# Power_Distribution_Board.net
KiCad netlist of a schematic drawn in EAGLE
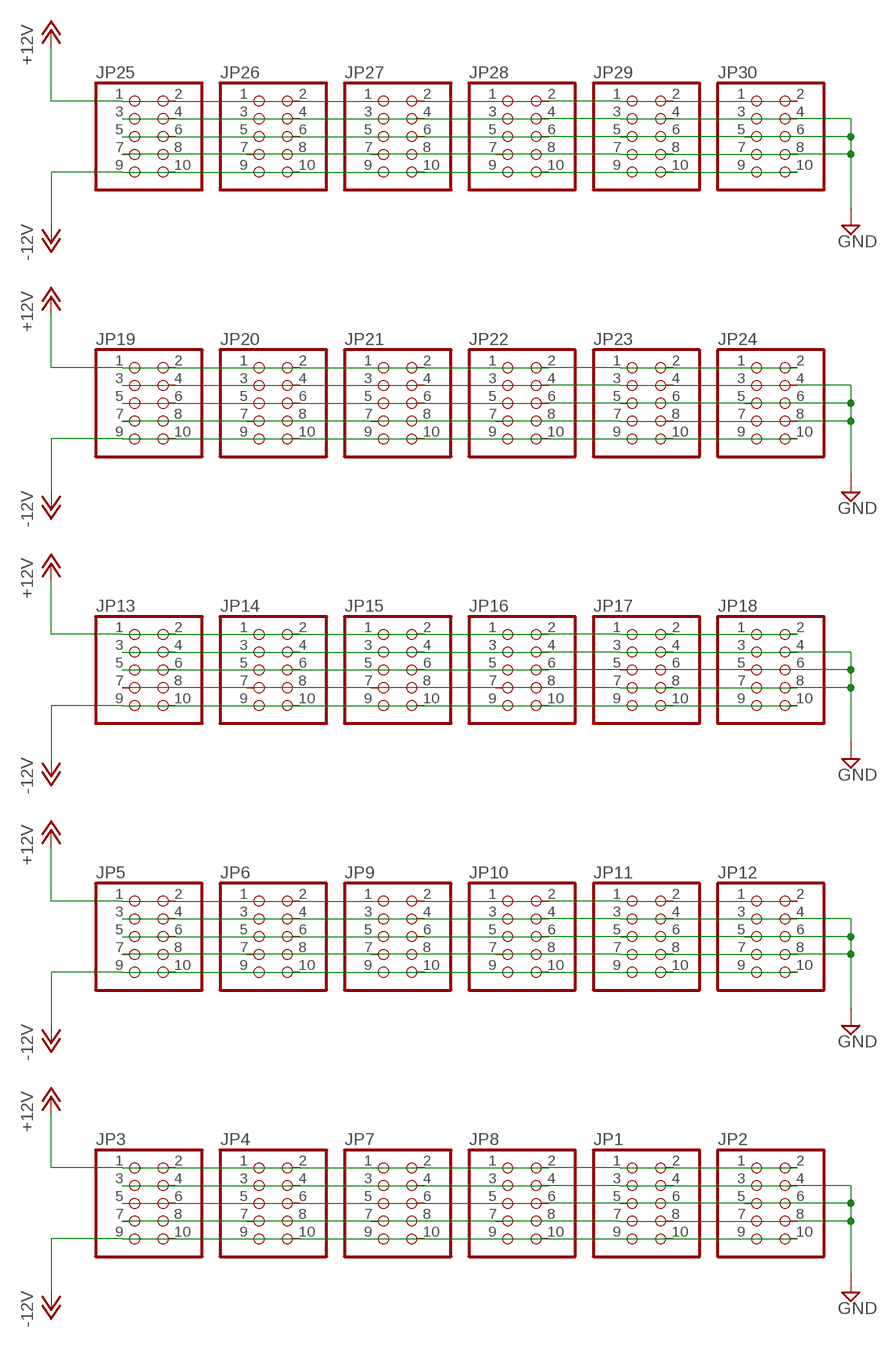
[diagram p0: schematic, sheet 1]

(export (version "E")
  (design (tool "Eeschema 10.0.6"))
  (components
    (comp (ref "JP1")
      (value "PINHD-2X5")
      (footprint "eagle-import:2X05")
      (libsource (lib "eagle-import") (part "PINHD-2X5"))
    )
    (comp (ref "JP2")
      (value "PINHD-2X5")
      (footprint "eagle-import:2X05")
      (libsource (lib "eagle-import") (part "PINHD-2X5"))
    )
    (comp (ref "JP3")
      (value "PINHD-2X5")
      (footprint "eagle-import:2X05")
      (libsource (lib "eagle-import") (part "PINHD-2X5"))
    )
    (comp (ref "JP4")
      (value "PINHD-2X5")
      (footprint "eagle-import:2X05")
      (libsource (lib "eagle-import") (part "PINHD-2X5"))
    )
    (comp (ref "JP5")
      (value "PINHD-2X5")
      (footprint "eagle-import:2X05")
      (libsource (lib "eagle-import") (part "PINHD-2X5"))
    )
    (comp (ref "JP6")
      (value "PINHD-2X5")
      (footprint "eagle-import:2X05")
      (libsource (lib "eagle-import") (part "PINHD-2X5"))
    )
    (comp (ref "JP7")
      (value "PINHD-2X5")
      (footprint "eagle-import:2X05")
      (libsource (lib "eagle-import") (part "PINHD-2X5"))
    )
    (comp (ref "JP8")
      (value "PINHD-2X5")
      (footprint "eagle-import:2X05")
      (libsource (lib "eagle-import") (part "PINHD-2X5"))
    )
    (comp (ref "JP9")
      (value "PINHD-2X5")
      (footprint "eagle-import:2X05")
      (libsource (lib "eagle-import") (part "PINHD-2X5"))
    )
    (comp (ref "JP10")
      (value "PINHD-2X5")
      (footprint "eagle-import:2X05")
      (libsource (lib "eagle-import") (part "PINHD-2X5"))
    )
    (comp (ref "JP11")
      (value "PINHD-2X5")
      (footprint "eagle-import:2X05")
      (libsource (lib "eagle-import") (part "PINHD-2X5"))
    )
    (comp (ref "JP12")
      (value "PINHD-2X5")
      (footprint "eagle-import:2X05")
      (libsource (lib "eagle-import") (part "PINHD-2X5"))
    )
    (comp (ref "JP13")
      (value "PINHD-2X5")
      (footprint "eagle-import:2X05")
      (libsource (lib "eagle-import") (part "PINHD-2X5"))
    )
    (comp (ref "JP14")
      (value "PINHD-2X5")
      (footprint "eagle-import:2X05")
      (libsource (lib "eagle-import") (part "PINHD-2X5"))
    )
    (comp (ref "JP15")
      (value "PINHD-2X5")
      (footprint "eagle-import:2X05")
      (libsource (lib "eagle-import") (part "PINHD-2X5"))
    )
    (comp (ref "JP16")
      (value "PINHD-2X5")
      (footprint "eagle-import:2X05")
      (libsource (lib "eagle-import") (part "PINHD-2X5"))
    )
    (comp (ref "JP17")
      (value "PINHD-2X5")
      (footprint "eagle-import:2X05")
      (libsource (lib "eagle-import") (part "PINHD-2X5"))
    )
    (comp (ref "JP18")
      (value "PINHD-2X5")
      (footprint "eagle-import:2X05")
      (libsource (lib "eagle-import") (part "PINHD-2X5"))
    )
    (comp (ref "JP19")
      (value "PINHD-2X5")
      (footprint "eagle-import:2X05")
      (libsource (lib "eagle-import") (part "PINHD-2X5"))
    )
    (comp (ref "JP20")
      (value "PINHD-2X5")
      (footprint "eagle-import:2X05")
      (libsource (lib "eagle-import") (part "PINHD-2X5"))
    )
    (comp (ref "JP21")
      (value "PINHD-2X5")
      (footprint "eagle-import:2X05")
      (libsource (lib "eagle-import") (part "PINHD-2X5"))
    )
    (comp (ref "JP22")
      (value "PINHD-2X5")
      (footprint "eagle-import:2X05")
      (libsource (lib "eagle-import") (part "PINHD-2X5"))
    )
    (comp (ref "JP23")
      (value "PINHD-2X5")
      (footprint "eagle-import:2X05")
      (libsource (lib "eagle-import") (part "PINHD-2X5"))
    )
    (comp (ref "JP24")
      (value "PINHD-2X5")
      (footprint "eagle-import:2X05")
      (libsource (lib "eagle-import") (part "PINHD-2X5"))
    )
    (comp (ref "JP25")
      (value "PINHD-2X5")
      (footprint "eagle-import:2X05")
      (libsource (lib "eagle-import") (part "PINHD-2X5"))
    )
    (comp (ref "JP26")
      (value "PINHD-2X5")
      (footprint "eagle-import:2X05")
      (libsource (lib "eagle-import") (part "PINHD-2X5"))
    )
    (comp (ref "JP27")
      (value "PINHD-2X5")
      (footprint "eagle-import:2X05")
      (libsource (lib "eagle-import") (part "PINHD-2X5"))
    )
    (comp (ref "JP28")
      (value "PINHD-2X5")
      (footprint "eagle-import:2X05")
      (libsource (lib "eagle-import") (part "PINHD-2X5"))
    )
    (comp (ref "JP29")
      (value "PINHD-2X5")
      (footprint "eagle-import:2X05")
      (libsource (lib "eagle-import") (part "PINHD-2X5"))
    )
    (comp (ref "JP30")
      (value "PINHD-2X5")
      (footprint "eagle-import:2X05")
      (libsource (lib "eagle-import") (part "PINHD-2X5"))
    )
  )
  (nets
    (net (code "1") (name "+12V") (class "Default")
      (node (ref "JP1") (pin "1") (pinfunction "1_1") (pintype "passive"))
      (node (ref "JP1") (pin "2") (pinfunction "2_2") (pintype "passive"))
      (node (ref "JP10") (pin "1") (pinfunction "1_1") (pintype "passive"))
      (node (ref "JP10") (pin "2") (pinfunction "2_2") (pintype "passive"))
      (node (ref "JP11") (pin "1") (pinfunction "1_1") (pintype "passive"))
      (node (ref "JP11") (pin "2") (pinfunction "2_2") (pintype "passive"))
      (node (ref "JP12") (pin "1") (pinfunction "1_1") (pintype "passive"))
      (node (ref "JP12") (pin "2") (pinfunction "2_2") (pintype "passive"))
      (node (ref "JP13") (pin "1") (pinfunction "1_1") (pintype "passive"))
      (node (ref "JP13") (pin "2") (pinfunction "2_2") (pintype "passive"))
      (node (ref "JP14") (pin "1") (pinfunction "1_1") (pintype "passive"))
      (node (ref "JP14") (pin "2") (pinfunction "2_2") (pintype "passive"))
      (node (ref "JP15") (pin "1") (pinfunction "1_1") (pintype "passive"))
      (node (ref "JP15") (pin "2") (pinfunction "2_2") (pintype "passive"))
      (node (ref "JP16") (pin "1") (pinfunction "1_1") (pintype "passive"))
      (node (ref "JP16") (pin "2") (pinfunction "2_2") (pintype "passive"))
      (node (ref "JP17") (pin "1") (pinfunction "1_1") (pintype "passive"))
      (node (ref "JP17") (pin "2") (pinfunction "2_2") (pintype "passive"))
      (node (ref "JP18") (pin "1") (pinfunction "1_1") (pintype "passive"))
      (node (ref "JP18") (pin "2") (pinfunction "2_2") (pintype "passive"))
      (node (ref "JP19") (pin "1") (pinfunction "1_1") (pintype "passive"))
      (node (ref "JP19") (pin "2") (pinfunction "2_2") (pintype "passive"))
      (node (ref "JP2") (pin "1") (pinfunction "1_1") (pintype "passive"))
      (node (ref "JP2") (pin "2") (pinfunction "2_2") (pintype "passive"))
      (node (ref "JP20") (pin "1") (pinfunction "1_1") (pintype "passive"))
      (node (ref "JP20") (pin "2") (pinfunction "2_2") (pintype "passive"))
      (node (ref "JP21") (pin "1") (pinfunction "1_1") (pintype "passive"))
      (node (ref "JP21") (pin "2") (pinfunction "2_2") (pintype "passive"))
      (node (ref "JP22") (pin "1") (pinfunction "1_1") (pintype "passive"))
      (node (ref "JP22") (pin "2") (pinfunction "2_2") (pintype "passive"))
      (node (ref "JP23") (pin "1") (pinfunction "1_1") (pintype "passive"))
      (node (ref "JP23") (pin "2") (pinfunction "2_2") (pintype "passive"))
      (node (ref "JP24") (pin "1") (pinfunction "1_1") (pintype "passive"))
      (node (ref "JP24") (pin "2") (pinfunction "2_2") (pintype "passive"))
      (node (ref "JP25") (pin "1") (pinfunction "1_1") (pintype "passive"))
      (node (ref "JP25") (pin "2") (pinfunction "2_2") (pintype "passive"))
      (node (ref "JP26") (pin "1") (pinfunction "1_1") (pintype "passive"))
      (node (ref "JP26") (pin "2") (pinfunction "2_2") (pintype "passive"))
      (node (ref "JP27") (pin "1") (pinfunction "1_1") (pintype "passive"))
      (node (ref "JP27") (pin "2") (pinfunction "2_2") (pintype "passive"))
      (node (ref "JP28") (pin "1") (pinfunction "1_1") (pintype "passive"))
      (node (ref "JP28") (pin "2") (pinfunction "2_2") (pintype "passive"))
      (node (ref "JP29") (pin "1") (pinfunction "1_1") (pintype "passive"))
      (node (ref "JP29") (pin "2") (pinfunction "2_2") (pintype "passive"))
      (node (ref "JP3") (pin "1") (pinfunction "1_1") (pintype "passive"))
      (node (ref "JP3") (pin "2") (pinfunction "2_2") (pintype "passive"))
      (node (ref "JP30") (pin "1") (pinfunction "1_1") (pintype "passive"))
      (node (ref "JP30") (pin "2") (pinfunction "2_2") (pintype "passive"))
      (node (ref "JP4") (pin "1") (pinfunction "1_1") (pintype "passive"))
      (node (ref "JP4") (pin "2") (pinfunction "2_2") (pintype "passive"))
      (node (ref "JP5") (pin "1") (pinfunction "1_1") (pintype "passive"))
      (node (ref "JP5") (pin "2") (pinfunction "2_2") (pintype "passive"))
      (node (ref "JP6") (pin "1") (pinfunction "1_1") (pintype "passive"))
      (node (ref "JP6") (pin "2") (pinfunction "2_2") (pintype "passive"))
      (node (ref "JP7") (pin "1") (pinfunction "1_1") (pintype "passive"))
      (node (ref "JP7") (pin "2") (pinfunction "2_2") (pintype "passive"))
      (node (ref "JP8") (pin "1") (pinfunction "1_1") (pintype "passive"))
      (node (ref "JP8") (pin "2") (pinfunction "2_2") (pintype "passive"))
      (node (ref "JP9") (pin "1") (pinfunction "1_1") (pintype "passive"))
      (node (ref "JP9") (pin "2") (pinfunction "2_2") (pintype "passive"))
    )
    (net (code "2") (name "-12V") (class "Default")
      (node (ref "JP1") (pin "10") (pinfunction "10_10") (pintype "passive"))
      (node (ref "JP1") (pin "9") (pinfunction "9_9") (pintype "passive"))
      (node (ref "JP10") (pin "10") (pinfunction "10_10") (pintype "passive"))
      (node (ref "JP10") (pin "9") (pinfunction "9_9") (pintype "passive"))
      (node (ref "JP11") (pin "10") (pinfunction "10_10") (pintype "passive"))
      (node (ref "JP11") (pin "9") (pinfunction "9_9") (pintype "passive"))
      (node (ref "JP12") (pin "10") (pinfunction "10_10") (pintype "passive"))
      (node (ref "JP12") (pin "9") (pinfunction "9_9") (pintype "passive"))
      (node (ref "JP13") (pin "10") (pinfunction "10_10") (pintype "passive"))
      (node (ref "JP13") (pin "9") (pinfunction "9_9") (pintype "passive"))
      (node (ref "JP14") (pin "10") (pinfunction "10_10") (pintype "passive"))
      (node (ref "JP14") (pin "9") (pinfunction "9_9") (pintype "passive"))
      (node (ref "JP15") (pin "10") (pinfunction "10_10") (pintype "passive"))
      (node (ref "JP15") (pin "9") (pinfunction "9_9") (pintype "passive"))
      (node (ref "JP16") (pin "10") (pinfunction "10_10") (pintype "passive"))
      (node (ref "JP16") (pin "9") (pinfunction "9_9") (pintype "passive"))
      (node (ref "JP17") (pin "10") (pinfunction "10_10") (pintype "passive"))
      (node (ref "JP17") (pin "9") (pinfunction "9_9") (pintype "passive"))
      (node (ref "JP18") (pin "10") (pinfunction "10_10") (pintype "passive"))
      (node (ref "JP18") (pin "9") (pinfunction "9_9") (pintype "passive"))
      (node (ref "JP19") (pin "10") (pinfunction "10_10") (pintype "passive"))
      (node (ref "JP19") (pin "9") (pinfunction "9_9") (pintype "passive"))
      (node (ref "JP2") (pin "10") (pinfunction "10_10") (pintype "passive"))
      (node (ref "JP2") (pin "9") (pinfunction "9_9") (pintype "passive"))
      (node (ref "JP20") (pin "10") (pinfunction "10_10") (pintype "passive"))
      (node (ref "JP20") (pin "9") (pinfunction "9_9") (pintype "passive"))
      (node (ref "JP21") (pin "10") (pinfunction "10_10") (pintype "passive"))
      (node (ref "JP21") (pin "9") (pinfunction "9_9") (pintype "passive"))
      (node (ref "JP22") (pin "10") (pinfunction "10_10") (pintype "passive"))
      (node (ref "JP22") (pin "9") (pinfunction "9_9") (pintype "passive"))
      (node (ref "JP23") (pin "10") (pinfunction "10_10") (pintype "passive"))
      (node (ref "JP23") (pin "9") (pinfunction "9_9") (pintype "passive"))
      (node (ref "JP24") (pin "10") (pinfunction "10_10") (pintype "passive"))
      (node (ref "JP24") (pin "9") (pinfunction "9_9") (pintype "passive"))
      (node (ref "JP25") (pin "10") (pinfunction "10_10") (pintype "passive"))
      (node (ref "JP25") (pin "9") (pinfunction "9_9") (pintype "passive"))
      (node (ref "JP26") (pin "10") (pinfunction "10_10") (pintype "passive"))
      (node (ref "JP26") (pin "9") (pinfunction "9_9") (pintype "passive"))
      (node (ref "JP27") (pin "10") (pinfunction "10_10") (pintype "passive"))
      (node (ref "JP27") (pin "9") (pinfunction "9_9") (pintype "passive"))
      (node (ref "JP28") (pin "10") (pinfunction "10_10") (pintype "passive"))
      (node (ref "JP28") (pin "9") (pinfunction "9_9") (pintype "passive"))
      (node (ref "JP29") (pin "10") (pinfunction "10_10") (pintype "passive"))
      (node (ref "JP29") (pin "9") (pinfunction "9_9") (pintype "passive"))
      (node (ref "JP3") (pin "10") (pinfunction "10_10") (pintype "passive"))
      (node (ref "JP3") (pin "9") (pinfunction "9_9") (pintype "passive"))
      (node (ref "JP30") (pin "10") (pinfunction "10_10") (pintype "passive"))
      (node (ref "JP30") (pin "9") (pinfunction "9_9") (pintype "passive"))
      (node (ref "JP4") (pin "10") (pinfunction "10_10") (pintype "passive"))
      (node (ref "JP4") (pin "9") (pinfunction "9_9") (pintype "passive"))
      (node (ref "JP5") (pin "10") (pinfunction "10_10") (pintype "passive"))
      (node (ref "JP5") (pin "9") (pinfunction "9_9") (pintype "passive"))
      (node (ref "JP6") (pin "10") (pinfunction "10_10") (pintype "passive"))
      (node (ref "JP6") (pin "9") (pinfunction "9_9") (pintype "passive"))
      (node (ref "JP7") (pin "10") (pinfunction "10_10") (pintype "passive"))
      (node (ref "JP7") (pin "9") (pinfunction "9_9") (pintype "passive"))
      (node (ref "JP8") (pin "10") (pinfunction "10_10") (pintype "passive"))
      (node (ref "JP8") (pin "9") (pinfunction "9_9") (pintype "passive"))
      (node (ref "JP9") (pin "10") (pinfunction "10_10") (pintype "passive"))
      (node (ref "JP9") (pin "9") (pinfunction "9_9") (pintype "passive"))
    )
    (net (code "3") (name "GND") (class "Default")
      (node (ref "JP1") (pin "3") (pinfunction "3_3") (pintype "passive"))
      (node (ref "JP1") (pin "4") (pinfunction "4_4") (pintype "passive"))
      (node (ref "JP1") (pin "5") (pinfunction "5_5") (pintype "passive"))
      (node (ref "JP1") (pin "6") (pinfunction "6_6") (pintype "passive"))
      (node (ref "JP1") (pin "7") (pinfunction "7_7") (pintype "passive"))
      (node (ref "JP1") (pin "8") (pinfunction "8_8") (pintype "passive"))
      (node (ref "JP10") (pin "3") (pinfunction "3_3") (pintype "passive"))
      (node (ref "JP10") (pin "4") (pinfunction "4_4") (pintype "passive"))
      (node (ref "JP10") (pin "5") (pinfunction "5_5") (pintype "passive"))
      (node (ref "JP10") (pin "6") (pinfunction "6_6") (pintype "passive"))
      (node (ref "JP10") (pin "7") (pinfunction "7_7") (pintype "passive"))
      (node (ref "JP10") (pin "8") (pinfunction "8_8") (pintype "passive"))
      (node (ref "JP11") (pin "3") (pinfunction "3_3") (pintype "passive"))
      (node (ref "JP11") (pin "4") (pinfunction "4_4") (pintype "passive"))
      (node (ref "JP11") (pin "5") (pinfunction "5_5") (pintype "passive"))
      (node (ref "JP11") (pin "6") (pinfunction "6_6") (pintype "passive"))
      (node (ref "JP11") (pin "7") (pinfunction "7_7") (pintype "passive"))
      (node (ref "JP11") (pin "8") (pinfunction "8_8") (pintype "passive"))
      (node (ref "JP12") (pin "3") (pinfunction "3_3") (pintype "passive"))
      (node (ref "JP12") (pin "4") (pinfunction "4_4") (pintype "passive"))
      (node (ref "JP12") (pin "5") (pinfunction "5_5") (pintype "passive"))
      (node (ref "JP12") (pin "6") (pinfunction "6_6") (pintype "passive"))
      (node (ref "JP12") (pin "7") (pinfunction "7_7") (pintype "passive"))
      (node (ref "JP12") (pin "8") (pinfunction "8_8") (pintype "passive"))
      (node (ref "JP13") (pin "3") (pinfunction "3_3") (pintype "passive"))
      (node (ref "JP13") (pin "4") (pinfunction "4_4") (pintype "passive"))
      (node (ref "JP13") (pin "5") (pinfunction "5_5") (pintype "passive"))
      (node (ref "JP13") (pin "6") (pinfunction "6_6") (pintype "passive"))
      (node (ref "JP13") (pin "7") (pinfunction "7_7") (pintype "passive"))
      (node (ref "JP13") (pin "8") (pinfunction "8_8") (pintype "passive"))
      (node (ref "JP14") (pin "3") (pinfunction "3_3") (pintype "passive"))
      (node (ref "JP14") (pin "4") (pinfunction "4_4") (pintype "passive"))
      (node (ref "JP14") (pin "5") (pinfunction "5_5") (pintype "passive"))
      (node (ref "JP14") (pin "6") (pinfunction "6_6") (pintype "passive"))
      (node (ref "JP14") (pin "7") (pinfunction "7_7") (pintype "passive"))
      (node (ref "JP14") (pin "8") (pinfunction "8_8") (pintype "passive"))
      (node (ref "JP15") (pin "3") (pinfunction "3_3") (pintype "passive"))
      (node (ref "JP15") (pin "4") (pinfunction "4_4") (pintype "passive"))
      (node (ref "JP15") (pin "5") (pinfunction "5_5") (pintype "passive"))
      (node (ref "JP15") (pin "6") (pinfunction "6_6") (pintype "passive"))
      (node (ref "JP15") (pin "7") (pinfunction "7_7") (pintype "passive"))
      (node (ref "JP15") (pin "8") (pinfunction "8_8") (pintype "passive"))
      (node (ref "JP16") (pin "3") (pinfunction "3_3") (pintype "passive"))
      (node (ref "JP16") (pin "4") (pinfunction "4_4") (pintype "passive"))
      (node (ref "JP16") (pin "5") (pinfunction "5_5") (pintype "passive"))
      (node (ref "JP16") (pin "6") (pinfunction "6_6") (pintype "passive"))
      (node (ref "JP16") (pin "7") (pinfunction "7_7") (pintype "passive"))
      (node (ref "JP16") (pin "8") (pinfunction "8_8") (pintype "passive"))
      (node (ref "JP17") (pin "3") (pinfunction "3_3") (pintype "passive"))
      (node (ref "JP17") (pin "4") (pinfunction "4_4") (pintype "passive"))
      (node (ref "JP17") (pin "5") (pinfunction "5_5") (pintype "passive"))
      (node (ref "JP17") (pin "6") (pinfunction "6_6") (pintype "passive"))
      (node (ref "JP17") (pin "7") (pinfunction "7_7") (pintype "passive"))
      (node (ref "JP17") (pin "8") (pinfunction "8_8") (pintype "passive"))
      (node (ref "JP18") (pin "3") (pinfunction "3_3") (pintype "passive"))
      (node (ref "JP18") (pin "4") (pinfunction "4_4") (pintype "passive"))
      (node (ref "JP18") (pin "5") (pinfunction "5_5") (pintype "passive"))
      (node (ref "JP18") (pin "6") (pinfunction "6_6") (pintype "passive"))
      (node (ref "JP18") (pin "7") (pinfunction "7_7") (pintype "passive"))
      (node (ref "JP18") (pin "8") (pinfunction "8_8") (pintype "passive"))
      (node (ref "JP19") (pin "3") (pinfunction "3_3") (pintype "passive"))
      (node (ref "JP19") (pin "4") (pinfunction "4_4") (pintype "passive"))
      (node (ref "JP19") (pin "5") (pinfunction "5_5") (pintype "passive"))
      (node (ref "JP19") (pin "6") (pinfunction "6_6") (pintype "passive"))
      (node (ref "JP19") (pin "7") (pinfunction "7_7") (pintype "passive"))
      (node (ref "JP19") (pin "8") (pinfunction "8_8") (pintype "passive"))
      (node (ref "JP2") (pin "3") (pinfunction "3_3") (pintype "passive"))
      (node (ref "JP2") (pin "4") (pinfunction "4_4") (pintype "passive"))
      (node (ref "JP2") (pin "5") (pinfunction "5_5") (pintype "passive"))
      (node (ref "JP2") (pin "6") (pinfunction "6_6") (pintype "passive"))
      (node (ref "JP2") (pin "7") (pinfunction "7_7") (pintype "passive"))
      (node (ref "JP2") (pin "8") (pinfunction "8_8") (pintype "passive"))
      (node (ref "JP20") (pin "3") (pinfunction "3_3") (pintype "passive"))
      (node (ref "JP20") (pin "4") (pinfunction "4_4") (pintype "passive"))
      (node (ref "JP20") (pin "5") (pinfunction "5_5") (pintype "passive"))
      (node (ref "JP20") (pin "6") (pinfunction "6_6") (pintype "passive"))
      (node (ref "JP20") (pin "7") (pinfunction "7_7") (pintype "passive"))
      (node (ref "JP20") (pin "8") (pinfunction "8_8") (pintype "passive"))
      (node (ref "JP21") (pin "3") (pinfunction "3_3") (pintype "passive"))
      (node (ref "JP21") (pin "4") (pinfunction "4_4") (pintype "passive"))
      (node (ref "JP21") (pin "5") (pinfunction "5_5") (pintype "passive"))
      (node (ref "JP21") (pin "6") (pinfunction "6_6") (pintype "passive"))
      (node (ref "JP21") (pin "7") (pinfunction "7_7") (pintype "passive"))
      (node (ref "JP21") (pin "8") (pinfunction "8_8") (pintype "passive"))
      (node (ref "JP22") (pin "3") (pinfunction "3_3") (pintype "passive"))
      (node (ref "JP22") (pin "4") (pinfunction "4_4") (pintype "passive"))
      (node (ref "JP22") (pin "5") (pinfunction "5_5") (pintype "passive"))
      (node (ref "JP22") (pin "6") (pinfunction "6_6") (pintype "passive"))
      (node (ref "JP22") (pin "7") (pinfunction "7_7") (pintype "passive"))
      (node (ref "JP22") (pin "8") (pinfunction "8_8") (pintype "passive"))
      (node (ref "JP23") (pin "3") (pinfunction "3_3") (pintype "passive"))
      (node (ref "JP23") (pin "4") (pinfunction "4_4") (pintype "passive"))
      (node (ref "JP23") (pin "5") (pinfunction "5_5") (pintype "passive"))
      (node (ref "JP23") (pin "6") (pinfunction "6_6") (pintype "passive"))
      (node (ref "JP23") (pin "7") (pinfunction "7_7") (pintype "passive"))
      (node (ref "JP23") (pin "8") (pinfunction "8_8") (pintype "passive"))
      (node (ref "JP24") (pin "3") (pinfunction "3_3") (pintype "passive"))
      (node (ref "JP24") (pin "4") (pinfunction "4_4") (pintype "passive"))
      (node (ref "JP24") (pin "5") (pinfunction "5_5") (pintype "passive"))
      (node (ref "JP24") (pin "6") (pinfunction "6_6") (pintype "passive"))
      (node (ref "JP24") (pin "7") (pinfunction "7_7") (pintype "passive"))
      (node (ref "JP24") (pin "8") (pinfunction "8_8") (pintype "passive"))
      (node (ref "JP25") (pin "3") (pinfunction "3_3") (pintype "passive"))
      (node (ref "JP25") (pin "4") (pinfunction "4_4") (pintype "passive"))
      (node (ref "JP25") (pin "5") (pinfunction "5_5") (pintype "passive"))
      (node (ref "JP25") (pin "6") (pinfunction "6_6") (pintype "passive"))
      (node (ref "JP25") (pin "7") (pinfunction "7_7") (pintype "passive"))
      (node (ref "JP25") (pin "8") (pinfunction "8_8") (pintype "passive"))
      (node (ref "JP26") (pin "3") (pinfunction "3_3") (pintype "passive"))
      (node (ref "JP26") (pin "4") (pinfunction "4_4") (pintype "passive"))
      (node (ref "JP26") (pin "5") (pinfunction "5_5") (pintype "passive"))
      (node (ref "JP26") (pin "6") (pinfunction "6_6") (pintype "passive"))
      (node (ref "JP26") (pin "7") (pinfunction "7_7") (pintype "passive"))
      (node (ref "JP26") (pin "8") (pinfunction "8_8") (pintype "passive"))
      (node (ref "JP27") (pin "3") (pinfunction "3_3") (pintype "passive"))
      (node (ref "JP27") (pin "4") (pinfunction "4_4") (pintype "passive"))
      (node (ref "JP27") (pin "5") (pinfunction "5_5") (pintype "passive"))
      (node (ref "JP27") (pin "6") (pinfunction "6_6") (pintype "passive"))
      (node (ref "JP27") (pin "7") (pinfunction "7_7") (pintype "passive"))
      (node (ref "JP27") (pin "8") (pinfunction "8_8") (pintype "passive"))
      (node (ref "JP28") (pin "3") (pinfunction "3_3") (pintype "passive"))
      (node (ref "JP28") (pin "4") (pinfunction "4_4") (pintype "passive"))
      (node (ref "JP28") (pin "5") (pinfunction "5_5") (pintype "passive"))
      (node (ref "JP28") (pin "6") (pinfunction "6_6") (pintype "passive"))
      (node (ref "JP28") (pin "7") (pinfunction "7_7") (pintype "passive"))
      (node (ref "JP28") (pin "8") (pinfunction "8_8") (pintype "passive"))
      (node (ref "JP29") (pin "3") (pinfunction "3_3") (pintype "passive"))
      (node (ref "JP29") (pin "4") (pinfunction "4_4") (pintype "passive"))
      (node (ref "JP29") (pin "5") (pinfunction "5_5") (pintype "passive"))
      (node (ref "JP29") (pin "6") (pinfunction "6_6") (pintype "passive"))
      (node (ref "JP29") (pin "7") (pinfunction "7_7") (pintype "passive"))
      (node (ref "JP29") (pin "8") (pinfunction "8_8") (pintype "passive"))
      (node (ref "JP3") (pin "3") (pinfunction "3_3") (pintype "passive"))
      (node (ref "JP3") (pin "4") (pinfunction "4_4") (pintype "passive"))
      (node (ref "JP3") (pin "5") (pinfunction "5_5") (pintype "passive"))
      (node (ref "JP3") (pin "6") (pinfunction "6_6") (pintype "passive"))
      (node (ref "JP3") (pin "7") (pinfunction "7_7") (pintype "passive"))
      (node (ref "JP3") (pin "8") (pinfunction "8_8") (pintype "passive"))
      (node (ref "JP30") (pin "3") (pinfunction "3_3") (pintype "passive"))
      (node (ref "JP30") (pin "4") (pinfunction "4_4") (pintype "passive"))
      (node (ref "JP30") (pin "5") (pinfunction "5_5") (pintype "passive"))
      (node (ref "JP30") (pin "6") (pinfunction "6_6") (pintype "passive"))
      (node (ref "JP30") (pin "7") (pinfunction "7_7") (pintype "passive"))
      (node (ref "JP30") (pin "8") (pinfunction "8_8") (pintype "passive"))
      (node (ref "JP4") (pin "3") (pinfunction "3_3") (pintype "passive"))
      (node (ref "JP4") (pin "4") (pinfunction "4_4") (pintype "passive"))
      (node (ref "JP4") (pin "5") (pinfunction "5_5") (pintype "passive"))
      (node (ref "JP4") (pin "6") (pinfunction "6_6") (pintype "passive"))
      (node (ref "JP4") (pin "7") (pinfunction "7_7") (pintype "passive"))
      (node (ref "JP4") (pin "8") (pinfunction "8_8") (pintype "passive"))
      (node (ref "JP5") (pin "3") (pinfunction "3_3") (pintype "passive"))
      (node (ref "JP5") (pin "4") (pinfunction "4_4") (pintype "passive"))
      (node (ref "JP5") (pin "5") (pinfunction "5_5") (pintype "passive"))
      (node (ref "JP5") (pin "6") (pinfunction "6_6") (pintype "passive"))
      (node (ref "JP5") (pin "7") (pinfunction "7_7") (pintype "passive"))
      (node (ref "JP5") (pin "8") (pinfunction "8_8") (pintype "passive"))
      (node (ref "JP6") (pin "3") (pinfunction "3_3") (pintype "passive"))
      (node (ref "JP6") (pin "4") (pinfunction "4_4") (pintype "passive"))
      (node (ref "JP6") (pin "5") (pinfunction "5_5") (pintype "passive"))
      (node (ref "JP6") (pin "6") (pinfunction "6_6") (pintype "passive"))
      (node (ref "JP6") (pin "7") (pinfunction "7_7") (pintype "passive"))
      (node (ref "JP6") (pin "8") (pinfunction "8_8") (pintype "passive"))
      (node (ref "JP7") (pin "3") (pinfunction "3_3") (pintype "passive"))
      (node (ref "JP7") (pin "4") (pinfunction "4_4") (pintype "passive"))
      (node (ref "JP7") (pin "5") (pinfunction "5_5") (pintype "passive"))
      (node (ref "JP7") (pin "6") (pinfunction "6_6") (pintype "passive"))
      (node (ref "JP7") (pin "7") (pinfunction "7_7") (pintype "passive"))
      (node (ref "JP7") (pin "8") (pinfunction "8_8") (pintype "passive"))
      (node (ref "JP8") (pin "3") (pinfunction "3_3") (pintype "passive"))
      (node (ref "JP8") (pin "4") (pinfunction "4_4") (pintype "passive"))
      (node (ref "JP8") (pin "5") (pinfunction "5_5") (pintype "passive"))
      (node (ref "JP8") (pin "6") (pinfunction "6_6") (pintype "passive"))
      (node (ref "JP8") (pin "7") (pinfunction "7_7") (pintype "passive"))
      (node (ref "JP8") (pin "8") (pinfunction "8_8") (pintype "passive"))
      (node (ref "JP9") (pin "3") (pinfunction "3_3") (pintype "passive"))
      (node (ref "JP9") (pin "4") (pinfunction "4_4") (pintype "passive"))
      (node (ref "JP9") (pin "5") (pinfunction "5_5") (pintype "passive"))
      (node (ref "JP9") (pin "6") (pinfunction "6_6") (pintype "passive"))
      (node (ref "JP9") (pin "7") (pinfunction "7_7") (pintype "passive"))
      (node (ref "JP9") (pin "8") (pinfunction "8_8") (pintype "passive"))
    )
  )
)
